# Connectors.net
KiCad netlist of a schematic drawn in Altium Designer
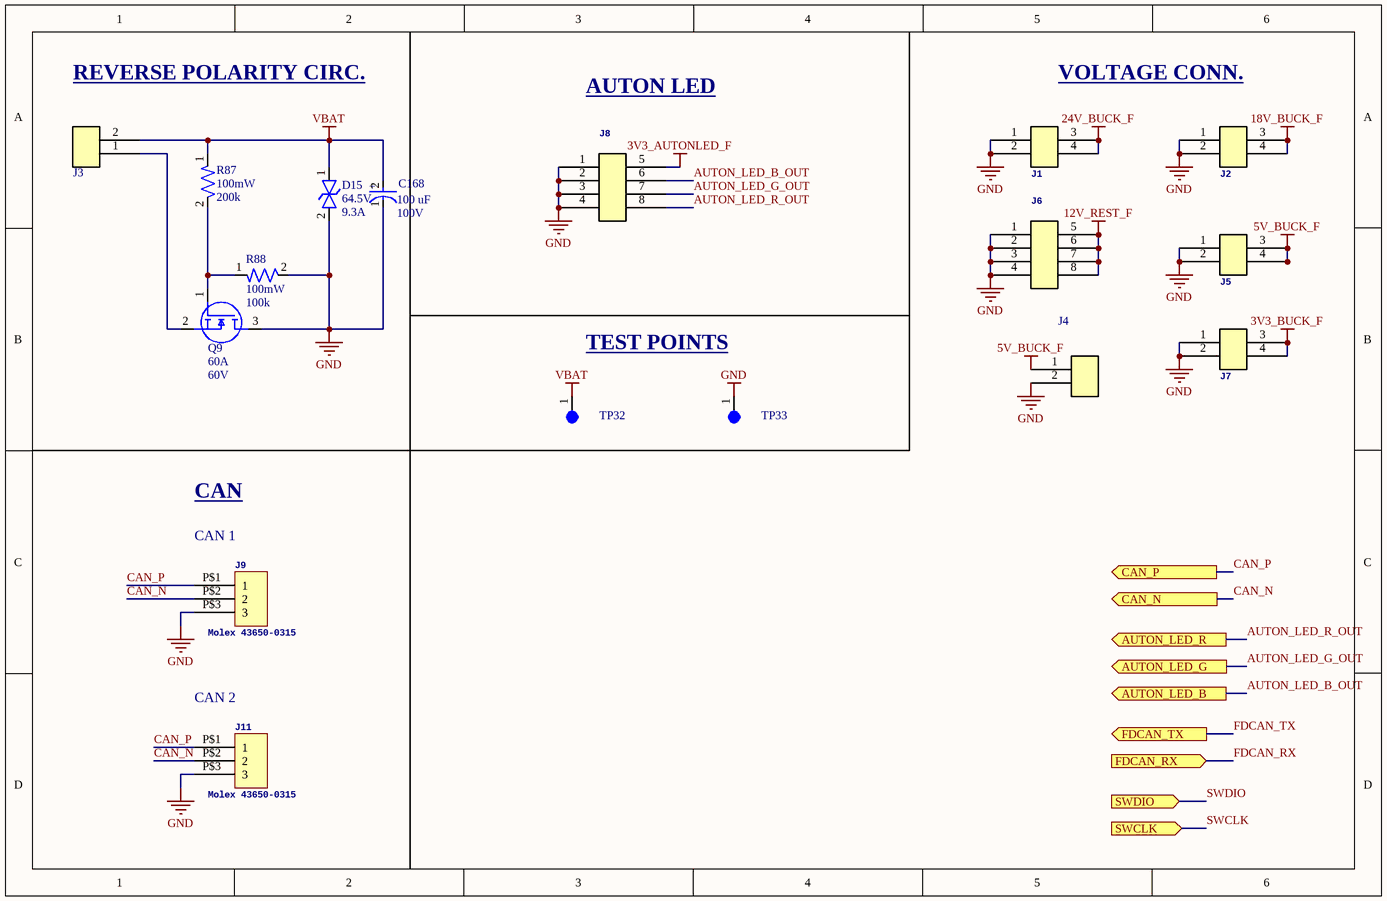
[diagram p0: Connectors.SchDoc]

(export (version "E")
  (design (tool "Eeschema 10.0.6"))
  (components
    (comp (ref "C168")
      (value "EEETK2A101AM")
      (footprint "CAP-100U-0001")
      (description "CAP ALUM 100UF 20% 100V SMD")
      (fields (field (name "VOLTAGE") "100V") (field (name "CAPACITANCE") "100 uF"))
      (libsource (lib "JLC_25") (part "CAP-100U-0001"))
    )
    (comp (ref "D15")
      (value "SMBJ40CA")
      (footprint "DO-214AA (SMBJ)")
      (description "TVS DIODE 40VWM 64.5VC DO214AA")
      (fields (field (name "VOLTAGE RATING") "64.5V") (field (name "CURRENT RATING") "9.3A"))
      (libsource (lib "JLC_25") (part "DIO-TVS-0001"))
    )
    (comp (ref "J1")
      (value "Molex 43045-0412")
      (footprint "CONN-4POS-0002")
      (description "CONN HEADER VERT 4POS 3MM")
      (libsource (lib "JLC_25") (part "CONN-4POS-0002"))
    )
    (comp (ref "J2")
      (value "Molex 43045-0412")
      (footprint "CONN-4POS-0002")
      (description "CONN HEADER VERT 4POS 3MM")
      (libsource (lib "JLC_25") (part "CONN-4POS-0002"))
    )
    (comp (ref "J3")
      (value "1546927-2")
      (footprint "CONN-1546927-2")
      (libsource (lib "JLC_25") (part "CONN-2POS-0003"))
    )
    (comp (ref "J4")
      (value "0436500215")
      (footprint "CONN-2POS-0002")
      (description "CONN HEADER VERT 2POS 3MM")
      (libsource (lib "JLC_25") (part "CONN-2POS-0002"))
    )
    (comp (ref "J5")
      (value "Molex 43045-0412")
      (footprint "CONN-4POS-0002")
      (description "CONN HEADER VERT 4POS 3MM")
      (libsource (lib "JLC_25") (part "CONN-4POS-0002"))
    )
    (comp (ref "J6")
      (value "Molex 43045-0812")
      (footprint "CONN-8POS-0001")
      (libsource (lib "JLC_25") (part "CONN-8POS-0001"))
    )
    (comp (ref "J7")
      (value "Molex 43045-0412")
      (footprint "CONN-4POS-0002")
      (description "CONN HEADER VERT 4POS 3MM")
      (libsource (lib "JLC_25") (part "CONN-4POS-0002"))
    )
    (comp (ref "J8")
      (value "Molex 43045-0812")
      (footprint "CONN-8POS-0001")
      (libsource (lib "JLC_25") (part "CONN-8POS-0001"))
    )
    (comp (ref "J9")
      (value "Molex 43650-0315")
      (footprint "43650-0315")
      (libsource (lib "Molex Microfit") (part "Micro-Fit Molex 3 Pin Vertical"))
    )
    (comp (ref "J11")
      (value "Molex 43650-0315")
      (footprint "43650-0315")
      (libsource (lib "Molex Microfit") (part "Micro-Fit Molex 3 Pin Vertical"))
    )
    (comp (ref "Q9")
      (value "CSD18543Q3AT")
      (footprint "IC-8VSONCLIP")
      (description "MOSFET N-CH 60V 12A/60A 8VSON")
      (fields (field (name "VOLTAGE") "60V") (field (name "CONTINUOUS CURRENT") "60A"))
      (libsource (lib "JLC_25") (part "NMOS-60A-0001"))
    )
    (comp (ref "R87")
      (value "RC0603FR-07200KL")
      (footprint "RES-0603")
      (description "RES SMD 200K OHM 1% 1/10W 0603")
      (fields
        (field (name "TOLERANCE") "1%")
        (field (name "POWER") "100mW")
        (field (name "RESISTANCE") "200k")
      )
      (libsource (lib "JLC_25") (part "RES-200k-0001"))
    )
    (comp (ref "R88")
      (value "RC0603FR-07100KL")
      (footprint "RES-0603")
      (description "RES SMD 100K OHM 1% 1/10W 0603")
      (fields
        (field (name "TOLERANCE") "1%")
        (field (name "POWER") "100mW")
        (field (name "RESISTANCE") "100k")
      )
      (libsource (lib "JLC_25") (part "RES-100k-0001"))
    )
    (comp (ref "TP32")
      (value "5003")
      (footprint "TEST-POINT-0001")
      (description "Oranange PC Test Point, Miniature Phoisphor Bronze Silver Plating Through Hole Mounting Type")
      (libsource (lib "*") (part "TEST-POINT-0001"))
    )
    (comp (ref "TP33")
      (value "5003")
      (footprint "TEST-POINT-0001")
      (description "Oranange PC Test Point, Miniature Phoisphor Bronze Silver Plating Through Hole Mounting Type")
      (libsource (lib "*") (part "TEST-POINT-0001"))
    )
  )
  (nets
    (net (code "1") (name "/AUTON_LED_B_OUT") (class "Default")
      (node (ref "J8") (pin "6") (pinfunction "6_6") (pintype "passive"))
    )
    (net (code "2") (name "/AUTON_LED_G_OUT") (class "Default")
      (node (ref "J8") (pin "7") (pinfunction "7_7") (pintype "passive"))
    )
    (net (code "3") (name "/AUTON_LED_R_OUT") (class "Default")
      (node (ref "J8") (pin "8") (pinfunction "8_8") (pintype "passive"))
    )
    (net (code "4") (name "/CAN_N") (class "Default")
      (node (ref "J11") (pin "P$2") (pinfunction "2_P$2") (pintype "passive"))
      (node (ref "J9") (pin "P$2") (pinfunction "2_P$2") (pintype "passive"))
    )
    (net (code "5") (name "/CAN_P") (class "Default")
      (node (ref "J11") (pin "P$1") (pinfunction "1_P$1") (pintype "passive"))
      (node (ref "J9") (pin "P$1") (pinfunction "1_P$1") (pintype "passive"))
    )
    (net (code "10") (name "3V3_AUTONLED_F") (class "Default")
      (node (ref "J8") (pin "5") (pinfunction "5_5") (pintype "passive"))
    )
    (net (code "11") (name "3V3_BUCK_F") (class "Default")
      (node (ref "J7") (pin "3") (pinfunction "3_3") (pintype "passive"))
      (node (ref "J7") (pin "4") (pinfunction "4_4") (pintype "passive"))
    )
    (net (code "12") (name "5V_BUCK_F") (class "Default")
      (node (ref "J4") (pin "1") (pinfunction "7_1") (pintype "passive"))
      (node (ref "J5") (pin "3") (pinfunction "3_3") (pintype "passive"))
      (node (ref "J5") (pin "4") (pinfunction "4_4") (pintype "passive"))
    )
    (net (code "13") (name "12V_REST_F") (class "Default")
      (node (ref "J6") (pin "5") (pinfunction "5_5") (pintype "passive"))
      (node (ref "J6") (pin "6") (pinfunction "6_6") (pintype "passive"))
      (node (ref "J6") (pin "7") (pinfunction "7_7") (pintype "passive"))
      (node (ref "J6") (pin "8") (pinfunction "8_8") (pintype "passive"))
    )
    (net (code "14") (name "18V_BUCK_F") (class "Default")
      (node (ref "J2") (pin "3") (pinfunction "3_3") (pintype "passive"))
      (node (ref "J2") (pin "4") (pinfunction "4_4") (pintype "passive"))
    )
    (net (code "15") (name "24V_BUCK_F") (class "Default")
      (node (ref "J1") (pin "3") (pinfunction "3_3") (pintype "passive"))
      (node (ref "J1") (pin "4") (pinfunction "4_4") (pintype "passive"))
    )
    (net (code "16") (name "GND") (class "Default")
      (node (ref "C168") (pin "1") (pinfunction "2_1") (pintype "passive"))
      (node (ref "D15") (pin "2") (pintype "passive"))
      (node (ref "J1") (pin "1") (pinfunction "1_1") (pintype "passive"))
      (node (ref "J1") (pin "2") (pinfunction "2_2") (pintype "passive"))
      (node (ref "J11") (pin "P$3") (pinfunction "3_P$3") (pintype "passive"))
      (node (ref "J2") (pin "1") (pinfunction "1_1") (pintype "passive"))
      (node (ref "J2") (pin "2") (pinfunction "2_2") (pintype "passive"))
      (node (ref "J4") (pin "2") (pinfunction "8_2") (pintype "passive"))
      (node (ref "J5") (pin "1") (pinfunction "1_1") (pintype "passive"))
      (node (ref "J5") (pin "2") (pinfunction "2_2") (pintype "passive"))
      (node (ref "J6") (pin "1") (pinfunction "7_1") (pintype "passive"))
      (node (ref "J6") (pin "2") (pinfunction "2_2") (pintype "passive"))
      (node (ref "J6") (pin "3") (pinfunction "3_3") (pintype "passive"))
      (node (ref "J6") (pin "4") (pinfunction "4_4") (pintype "passive"))
      (node (ref "J7") (pin "1") (pinfunction "1_1") (pintype "passive"))
      (node (ref "J7") (pin "2") (pinfunction "2_2") (pintype "passive"))
      (node (ref "J8") (pin "1") (pinfunction "7_1") (pintype "passive"))
      (node (ref "J8") (pin "2") (pinfunction "2_2") (pintype "passive"))
      (node (ref "J8") (pin "3") (pinfunction "3_3") (pintype "passive"))
      (node (ref "J8") (pin "4") (pinfunction "4_4") (pintype "passive"))
      (node (ref "J9") (pin "P$3") (pinfunction "3_P$3") (pintype "passive"))
      (node (ref "Q9") (pin "3") (pinfunction "D_3") (pintype "passive"))
      (node (ref "R88") (pin "2") (pinfunction "2_2") (pintype "passive"))
      (node (ref "TP33") (pin "1") (pinfunction "0_1") (pintype "passive"))
    )
    (net (code "17") (name "Net-(J3-7)") (class "Default")
      (node (ref "J3") (pin "1") (pinfunction "7_1") (pintype "passive"))
      (node (ref "Q9") (pin "2") (pinfunction "S_2") (pintype "passive"))
    )
    (net (code "18") (name "Net-(Q9-G)") (class "Default")
      (node (ref "Q9") (pin "1") (pinfunction "G_1") (pintype "passive"))
      (node (ref "R87") (pin "2") (pinfunction "2_2") (pintype "passive"))
      (node (ref "R88") (pin "1") (pinfunction "1_1") (pintype "passive"))
    )
    (net (code "19") (name "VBAT") (class "Default")
      (node (ref "C168") (pin "2") (pinfunction "1_2") (pintype "passive"))
      (node (ref "D15") (pin "1") (pintype "passive"))
      (node (ref "J3") (pin "2") (pinfunction "8_2") (pintype "passive"))
      (node (ref "R87") (pin "1") (pinfunction "1_1") (pintype "passive"))
      (node (ref "TP32") (pin "1") (pinfunction "0_1") (pintype "passive"))
    )
  )
)
